# 5_Magnetorquer_Drivers.net
KiCad netlist of a schematic drawn in Altium Designer
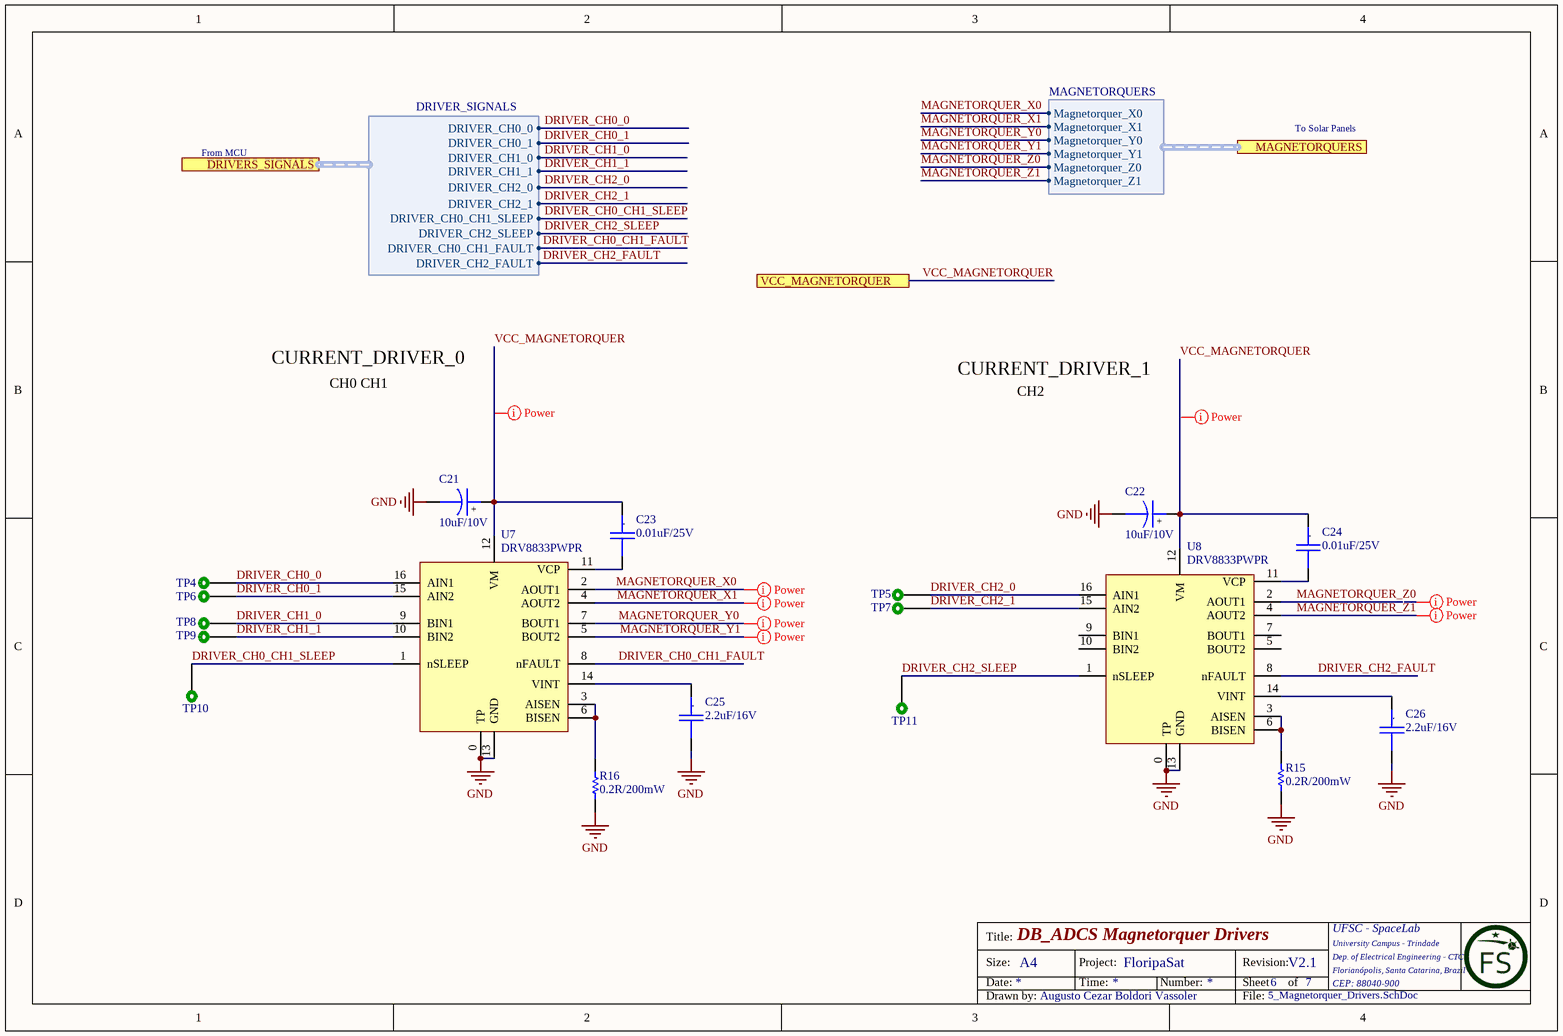
[diagram p0: 5_Magnetorquer_Drivers.SchDoc]

(export (version "E")
  (design (tool "Eeschema 10.0.6"))
  (components
    (comp (ref "C21")
      (value "10uF/10V")
      (footprint "CC0805_Tantalum")
      (description "CAP Tantalum 10uF 6.3V 10% 0805")
      (fields (field (name "PARTNUMBER") "TPSR106K006R1000"))
      (libsource (lib "PCB_Eng_Model_OBDH_2") (part "Cap_Tant_SMD_10uF_6V3_0805"))
    )
    (comp (ref "C22")
      (value "10uF/10V")
      (footprint "CC0805_Tantalum")
      (description "CAP Tantalum 10uF 6.3V 10% 0805")
      (fields (field (name "PARTNUMBER") "TPSR106K006R1000"))
      (libsource (lib "PCB_Eng_Model_OBDH_2") (part "Cap_Tant_SMD_10uF_6V3_0805"))
    )
    (comp (ref "C23")
      (value "0.01uF/25V")
      (footprint "CC0805")
      (description "CAP CER 0.01uF 25V 10% X7R 0805")
      (fields (field (name "PARTNUMBER") "CL21B103KAANNNC"))
      (libsource (lib "PCB_Eng_Model_OBDH_2") (part "Cap_Cer_X7R_0.01uF_50V_0805"))
    )
    (comp (ref "C24")
      (value "0.01uF/25V")
      (footprint "CC0805")
      (description "CAP CER 0.01uF 25V 10% X7R 0805")
      (fields (field (name "PARTNUMBER") "CL21B103KAANNNC"))
      (libsource (lib "PCB_Eng_Model_OBDH_2") (part "Cap_Cer_X7R_0.01uF_50V_0805"))
    )
    (comp (ref "C25")
      (value "2.2uF/16V")
      (footprint "CC0805")
      (description "CAP CER 2.2uF 16V 0805")
      (fields (field (name "PARTNUMBER") "C2012X7R1C225K125AB"))
      (libsource (lib "PCB_Eng_Model_OBDH_2") (part "Cap_Cer_X7R_2.2uF_16V_0805"))
    )
    (comp (ref "C26")
      (value "2.2uF/16V")
      (footprint "CC0805")
      (description "CAP CER 2.2uF 16V 0805")
      (fields (field (name "PARTNUMBER") "C2012X7R1C225K125AB"))
      (libsource (lib "PCB_Eng_Model_OBDH_2") (part "Cap_Cer_X7R_2.2uF_16V_0805"))
    )
    (comp (ref "R15")
      (value "0.2R/200mW")
      (footprint "0805-LED")
      (description "RES 0.2 OHM - 0.2W 1% 0805")
      (fields (field (name "PARTNUMBER") "RL1220S-R20-F"))
      (libsource (lib "PCB_Eng_Model_OBDH_2") (part "R0.015R_1%_0.5W_0805"))
    )
    (comp (ref "R16")
      (value "0.2R/200mW")
      (footprint "0805-LED")
      (description "RES 0.2 OHM - 0.2W 1% 0805")
      (fields (field (name "PARTNUMBER") "RL1220S-R20-F"))
      (libsource (lib "PCB_Eng_Model_OBDH_2") (part "R0.015R_1%_0.5W_0805"))
    )
    (comp (ref "TP4")
      (value "TEST_POINT_2")
      (footprint "TEST_POINT_2")
      (description "Test point")
      (libsource (lib "PCB_Eng_Model_OBDH_2") (part "TEST_POINT_2"))
    )
    (comp (ref "TP5")
      (value "TEST_POINT_2")
      (footprint "TEST_POINT_2")
      (description "Test point")
      (libsource (lib "PCB_Eng_Model_OBDH_2") (part "TEST_POINT_2"))
    )
    (comp (ref "TP6")
      (value "TEST_POINT_2")
      (footprint "TEST_POINT_2")
      (description "Test point")
      (libsource (lib "PCB_Eng_Model_OBDH_2") (part "TEST_POINT_2"))
    )
    (comp (ref "TP7")
      (value "TEST_POINT_2")
      (footprint "TEST_POINT_2")
      (description "Test point")
      (libsource (lib "PCB_Eng_Model_OBDH_2") (part "TEST_POINT_2"))
    )
    (comp (ref "TP8")
      (value "TEST_POINT_2")
      (footprint "TEST_POINT_2")
      (description "Test point")
      (libsource (lib "PCB_Eng_Model_OBDH_2") (part "TEST_POINT_2"))
    )
    (comp (ref "TP9")
      (value "TEST_POINT_2")
      (footprint "TEST_POINT_2")
      (description "Test point")
      (libsource (lib "PCB_Eng_Model_OBDH_2") (part "TEST_POINT_2"))
    )
    (comp (ref "TP10")
      (value "TEST_POINT_2")
      (footprint "TEST_POINT_2")
      (description "Test point")
      (libsource (lib "PCB_Eng_Model_OBDH_2") (part "TEST_POINT_2"))
    )
    (comp (ref "TP11")
      (value "TEST_POINT_2")
      (footprint "TEST_POINT_2")
      (description "Test point")
      (libsource (lib "PCB_Eng_Model_OBDH_2") (part "TEST_POINT_2"))
    )
    (comp (ref "U7")
      (value "DRV8833PWPR")
      (footprint "16TTSSOP")
      (libsource (lib "FloripaSatSchlib") (part "DRV8833PWPR"))
    )
    (comp (ref "U8")
      (value "DRV8833PWPR")
      (footprint "16TTSSOP")
      (libsource (lib "FloripaSatSchlib") (part "DRV8833PWPR"))
    )
  )
  (nets
    (net (code "3") (name "/DRIVER_CH0_0") (class "Default")
      (node (ref "TP4") (pin "1") (pinfunction "1_1") (pintype "passive"))
      (node (ref "U7") (pin "16") (pinfunction "AIN1_16") (pintype "passive"))
    )
    (net (code "4") (name "/DRIVER_CH0_1") (class "Default")
      (node (ref "TP6") (pin "1") (pinfunction "1_1") (pintype "passive"))
      (node (ref "U7") (pin "15") (pinfunction "AIN2_15") (pintype "passive"))
    )
    (net (code "5") (name "/DRIVER_CH0_CH1_FAULT") (class "Default")
      (node (ref "U7") (pin "8") (pinfunction "nFAULT_8") (pintype "passive"))
    )
    (net (code "6") (name "/DRIVER_CH0_CH1_SLEEP") (class "Default")
      (node (ref "TP10") (pin "1") (pinfunction "1_1") (pintype "passive"))
      (node (ref "U7") (pin "1") (pinfunction "nSLEEP_1") (pintype "passive"))
    )
    (net (code "7") (name "/DRIVER_CH1_0") (class "Default")
      (node (ref "TP8") (pin "1") (pinfunction "1_1") (pintype "passive"))
      (node (ref "U7") (pin "9") (pinfunction "BIN1_9") (pintype "passive"))
    )
    (net (code "8") (name "/DRIVER_CH1_1") (class "Default")
      (node (ref "TP9") (pin "1") (pinfunction "1_1") (pintype "passive"))
      (node (ref "U7") (pin "10") (pinfunction "BIN2_10") (pintype "passive"))
    )
    (net (code "9") (name "/DRIVER_CH2_0") (class "Default")
      (node (ref "TP5") (pin "1") (pinfunction "1_1") (pintype "passive"))
      (node (ref "U8") (pin "16") (pinfunction "AIN1_16") (pintype "passive"))
    )
    (net (code "10") (name "/DRIVER_CH2_1") (class "Default")
      (node (ref "TP7") (pin "1") (pinfunction "1_1") (pintype "passive"))
      (node (ref "U8") (pin "15") (pinfunction "AIN2_15") (pintype "passive"))
    )
    (net (code "11") (name "/DRIVER_CH2_FAULT") (class "Default")
      (node (ref "U8") (pin "8") (pinfunction "nFAULT_8") (pintype "passive"))
    )
    (net (code "12") (name "/DRIVER_CH2_SLEEP") (class "Default")
      (node (ref "TP11") (pin "1") (pinfunction "1_1") (pintype "passive"))
      (node (ref "U8") (pin "1") (pinfunction "nSLEEP_1") (pintype "passive"))
    )
    (net (code "13") (name "/MAGNETORQUER_X0") (class "Default")
      (node (ref "U7") (pin "2") (pinfunction "AOUT1_2") (pintype "passive"))
    )
    (net (code "14") (name "/MAGNETORQUER_X1") (class "Default")
      (node (ref "U7") (pin "4") (pinfunction "AOUT2_4") (pintype "passive"))
    )
    (net (code "15") (name "/MAGNETORQUER_Y0") (class "Default")
      (node (ref "U7") (pin "7") (pinfunction "BOUT1_7") (pintype "passive"))
    )
    (net (code "16") (name "/MAGNETORQUER_Y1") (class "Default")
      (node (ref "U7") (pin "5") (pinfunction "BOUT2_5") (pintype "passive"))
    )
    (net (code "17") (name "/MAGNETORQUER_Z0") (class "Default")
      (node (ref "U8") (pin "2") (pinfunction "AOUT1_2") (pintype "passive"))
    )
    (net (code "18") (name "/MAGNETORQUER_Z1") (class "Default")
      (node (ref "U8") (pin "4") (pinfunction "AOUT2_4") (pintype "passive"))
    )
    (net (code "19") (name "/VCC_MAGNETORQUER") (class "Default")
      (node (ref "C21") (pin "1") (pinfunction "1_1") (pintype "passive"))
      (node (ref "C22") (pin "1") (pinfunction "1_1") (pintype "passive"))
      (node (ref "C23") (pin "1") (pinfunction "1_1") (pintype "passive"))
      (node (ref "C24") (pin "1") (pinfunction "1_1") (pintype "passive"))
      (node (ref "U7") (pin "12") (pinfunction "VM_12") (pintype "passive"))
      (node (ref "U8") (pin "12") (pinfunction "VM_12") (pintype "passive"))
    )
    (net (code "22") (name "GND") (class "Default")
      (node (ref "C21") (pin "2") (pinfunction "2_2") (pintype "passive"))
      (node (ref "C22") (pin "2") (pinfunction "2_2") (pintype "passive"))
      (node (ref "C25") (pin "2") (pinfunction "2_2") (pintype "passive"))
      (node (ref "C26") (pin "2") (pinfunction "2_2") (pintype "passive"))
      (node (ref "R15") (pin "1") (pinfunction "1_1") (pintype "passive"))
      (node (ref "R16") (pin "1") (pinfunction "1_1") (pintype "passive"))
      (node (ref "U7") (pin "0") (pinfunction "TP_0") (pintype "passive"))
      (node (ref "U7") (pin "13") (pinfunction "GND_13") (pintype "passive"))
      (node (ref "U8") (pin "0") (pinfunction "TP_0") (pintype "passive"))
      (node (ref "U8") (pin "13") (pinfunction "GND_13") (pintype "passive"))
    )
    (net (code "23") (name "Net-(U7-AISEN)") (class "Default")
      (node (ref "R16") (pin "2") (pinfunction "2_2") (pintype "passive"))
      (node (ref "U7") (pin "3") (pinfunction "AISEN_3") (pintype "passive"))
      (node (ref "U7") (pin "6") (pinfunction "BISEN_6") (pintype "passive"))
    )
    (net (code "24") (name "Net-(U7-VCP)") (class "Default")
      (node (ref "C23") (pin "2") (pinfunction "2_2") (pintype "passive"))
      (node (ref "U7") (pin "11") (pinfunction "VCP_11") (pintype "passive"))
    )
    (net (code "25") (name "Net-(U7-VINT)") (class "Default")
      (node (ref "C25") (pin "1") (pinfunction "1_1") (pintype "passive"))
      (node (ref "U7") (pin "14") (pinfunction "VINT_14") (pintype "passive"))
    )
    (net (code "26") (name "Net-(U8-AISEN)") (class "Default")
      (node (ref "R15") (pin "2") (pinfunction "2_2") (pintype "passive"))
      (node (ref "U8") (pin "3") (pinfunction "AISEN_3") (pintype "passive"))
      (node (ref "U8") (pin "6") (pinfunction "BISEN_6") (pintype "passive"))
    )
    (net (code "27") (name "Net-(U8-VCP)") (class "Default")
      (node (ref "C24") (pin "2") (pinfunction "2_2") (pintype "passive"))
      (node (ref "U8") (pin "11") (pinfunction "VCP_11") (pintype "passive"))
    )
    (net (code "28") (name "Net-(U8-VINT)") (class "Default")
      (node (ref "C26") (pin "1") (pinfunction "1_1") (pintype "passive"))
      (node (ref "U8") (pin "14") (pinfunction "VINT_14") (pintype "passive"))
    )
    (net (code "29") (name "unconnected-(U8-BIN1-Pad9)") (class "Default")
      (node (ref "U8") (pin "9") (pinfunction "BIN1_9") (pintype "passive"))
    )
    (net (code "30") (name "unconnected-(U8-BIN2-Pad10)") (class "Default")
      (node (ref "U8") (pin "10") (pinfunction "BIN2_10") (pintype "passive"))
    )
    (net (code "31") (name "unconnected-(U8-BOUT1-Pad7)") (class "Default")
      (node (ref "U8") (pin "7") (pinfunction "BOUT1_7") (pintype "passive"))
    )
    (net (code "32") (name "unconnected-(U8-BOUT2-Pad5)") (class "Default")
      (node (ref "U8") (pin "5") (pinfunction "BOUT2_5") (pintype "passive"))
    )
  )
)
